# Pure_LFO.net
KiCad netlist of a schematic drawn in EAGLE
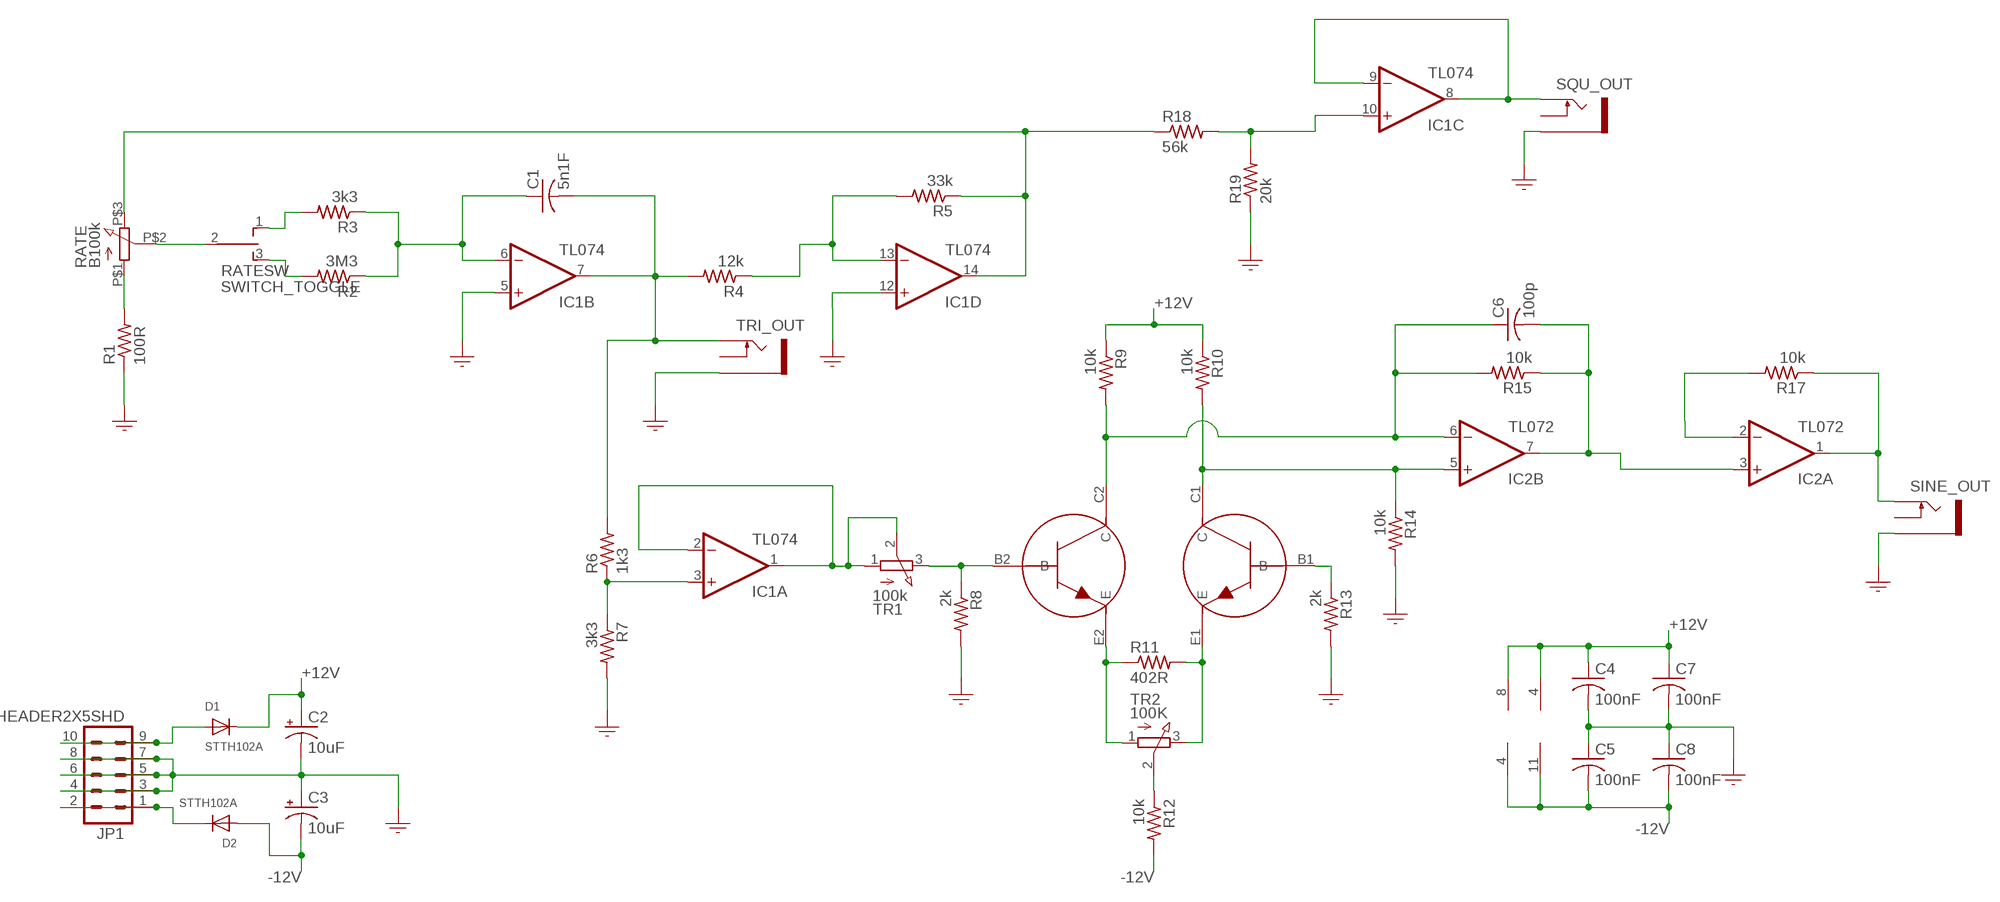
[diagram p0: schematic, sheet 1]

(export (version "E")
  (design (tool "Eeschema 10.0.6"))
  (components
    (comp (ref "C1")
      (value "5n1F")
      (footprint "eagle-import:C0805")
      (libsource (lib "eagle-import") (part "CAPACITOR-USC0805"))
    )
    (comp (ref "C2")
      (value "10uF")
      (footprint "eagle-import:153CLV-0505")
      (libsource (lib "eagle-import") (part "CAPACITOR_POL-US153CLV-0505"))
    )
    (comp (ref "C3")
      (value "10uF")
      (footprint "eagle-import:153CLV-0505")
      (libsource (lib "eagle-import") (part "CAPACITOR_POL-US153CLV-0505"))
    )
    (comp (ref "C4")
      (value "100nF")
      (footprint "eagle-import:C0805")
      (libsource (lib "eagle-import") (part "CAPACITOR-USC0805"))
    )
    (comp (ref "C5")
      (value "100nF")
      (footprint "eagle-import:C0805")
      (libsource (lib "eagle-import") (part "CAPACITOR-USC0805"))
    )
    (comp (ref "C6")
      (value "100p")
      (footprint "eagle-import:C0805")
      (libsource (lib "eagle-import") (part "CAPACITOR-USC0805"))
    )
    (comp (ref "C7")
      (value "100nF")
      (footprint "eagle-import:C0805")
      (libsource (lib "eagle-import") (part "CAPACITOR-USC0805"))
    )
    (comp (ref "C8")
      (value "100nF")
      (footprint "eagle-import:C0805")
      (libsource (lib "eagle-import") (part "CAPACITOR-USC0805"))
    )
    (comp (ref "D1")
      (value "STTH102A")
      (footprint "eagle-import:SMADIODE")
      (libsource (lib "eagle-import") (part "DIODESMA"))
    )
    (comp (ref "D2")
      (value "STTH102A")
      (footprint "eagle-import:SMADIODE")
      (libsource (lib "eagle-import") (part "DIODESMA"))
    )
    (comp (ref "IC1")
      (value "TL074")
      (footprint "eagle-import:SO14")
      (libsource (lib "eagle-import") (part "OPAMP_QUADD"))
    )
    (comp (ref "IC2")
      (value "TL072")
      (footprint "eagle-import:SO08")
      (libsource (lib "eagle-import") (part "OPAMP_DUALD"))
    )
    (comp (ref "JP1")
      (value "HEADER2X5SHD")
      (footprint "eagle-import:2X5-SHROUDED")
      (libsource (lib "eagle-import") (part "HEADER2X5SHD"))
    )
    (comp (ref "R1")
      (value "100R")
      (footprint "eagle-import:R0805")
      (libsource (lib "eagle-import") (part "RESISTOR_USR0805"))
    )
    (comp (ref "R2")
      (value "3M3")
      (footprint "eagle-import:R0805")
      (libsource (lib "eagle-import") (part "RESISTOR_USR0805"))
    )
    (comp (ref "R3")
      (value "3k3")
      (footprint "eagle-import:R0805")
      (libsource (lib "eagle-import") (part "RESISTOR_USR0805"))
    )
    (comp (ref "R4")
      (value "12k")
      (footprint "eagle-import:R0805")
      (libsource (lib "eagle-import") (part "RESISTOR_USR0805"))
    )
    (comp (ref "R5")
      (value "33k")
      (footprint "eagle-import:R0805")
      (libsource (lib "eagle-import") (part "RESISTOR_USR0805"))
    )
    (comp (ref "R6")
      (value "1k3")
      (footprint "eagle-import:R0805")
      (libsource (lib "eagle-import") (part "RESISTOR_USR0805"))
    )
    (comp (ref "R7")
      (value "3k3")
      (footprint "eagle-import:R0805")
      (libsource (lib "eagle-import") (part "RESISTOR_USR0805"))
    )
    (comp (ref "R8")
      (value "2k")
      (footprint "eagle-import:R0805")
      (libsource (lib "eagle-import") (part "RESISTOR_USR0805"))
    )
    (comp (ref "R9")
      (value "10k")
      (footprint "eagle-import:R0805")
      (libsource (lib "eagle-import") (part "RESISTOR_USR0805"))
    )
    (comp (ref "R10")
      (value "10k")
      (footprint "eagle-import:R0805")
      (libsource (lib "eagle-import") (part "RESISTOR_USR0805"))
    )
    (comp (ref "R11")
      (value "402R")
      (footprint "eagle-import:R0805")
      (libsource (lib "eagle-import") (part "RESISTOR_USR0805"))
    )
    (comp (ref "R12")
      (value "10k")
      (footprint "eagle-import:R0805")
      (libsource (lib "eagle-import") (part "RESISTOR_USR0805"))
    )
    (comp (ref "R13")
      (value "2k")
      (footprint "eagle-import:R0805")
      (libsource (lib "eagle-import") (part "RESISTOR_USR0805"))
    )
    (comp (ref "R14")
      (value "10k")
      (footprint "eagle-import:R0805")
      (libsource (lib "eagle-import") (part "RESISTOR_USR0805"))
    )
    (comp (ref "R15")
      (value "10k")
      (footprint "eagle-import:R0805")
      (libsource (lib "eagle-import") (part "RESISTOR_USR0805"))
    )
    (comp (ref "R17")
      (value "10k")
      (footprint "eagle-import:R0805")
      (libsource (lib "eagle-import") (part "RESISTOR_USR0805"))
    )
    (comp (ref "R18")
      (value "56k")
      (footprint "eagle-import:R0805")
      (libsource (lib "eagle-import") (part "RESISTOR_USR0805"))
    )
    (comp (ref "R19")
      (value "20k")
      (footprint "eagle-import:R0805")
      (libsource (lib "eagle-import") (part "RESISTOR_USR0805"))
    )
    (comp (ref "RATE")
      (value "B100k")
      (footprint "eagle-import:POTENTIOMETER_9MM")
      (libsource (lib "eagle-import") (part "RESISTOR_VARIABLE9MM_POT"))
    )
    (comp (ref "RATESW")
      (value "SWITCH_TOGGLE")
      (footprint "eagle-import:TOGGLE_SW")
      (libsource (lib "eagle-import") (part "SWITCH_TOGGLE"))
    )
    (comp (ref "SINE_OUT")
      (value "SOCKET_MONO_3.5MMPJ301M-12")
      (footprint "eagle-import:PJ301M-12")
      (libsource (lib "eagle-import") (part "SOCKET_MONO_3.5MMPJ301M-12"))
    )
    (comp (ref "SQU_OUT")
      (value "SOCKET_MONO_3.5MMPJ301M-12")
      (footprint "eagle-import:PJ301M-12")
      (libsource (lib "eagle-import") (part "SOCKET_MONO_3.5MMPJ301M-12"))
    )
    (comp (ref "T3")
      (value "DMMT3904W-7-F")
      (footprint "eagle-import:TRANS_PAIR")
      (libsource (lib "eagle-import") (part "TRANSISTOR_PAIR_NPN"))
    )
    (comp (ref "TR1")
      (value "100k")
      (footprint "eagle-import:TRIMMER_TH")
      (libsource (lib "eagle-import") (part "RESISTOR_VARIABLETRIMMER_TH"))
    )
    (comp (ref "TR2")
      (value "100K")
      (footprint "eagle-import:TRIMMER_TH")
      (libsource (lib "eagle-import") (part "RESISTOR_VARIABLETRIMMER_TH"))
    )
    (comp (ref "TRI_OUT")
      (value "SOCKET_MONO_3.5MMPJ301M-12")
      (footprint "eagle-import:PJ301M-12")
      (libsource (lib "eagle-import") (part "SOCKET_MONO_3.5MMPJ301M-12"))
    )
  )
  (nets
    (net (code "1") (name "/+12V") (class "Default")
      (node (ref "C2") (pin "+") (pinfunction "+_+") (pintype "passive"))
      (node (ref "C4") (pin "1") (pinfunction "1_1") (pintype "passive"))
      (node (ref "C7") (pin "1") (pinfunction "1_1") (pintype "passive"))
      (node (ref "D1") (pin "C") (pinfunction "C_C") (pintype "passive"))
      (node (ref "IC1") (pin "4") (pinfunction "V+_4") (pintype "power_in"))
      (node (ref "IC2") (pin "8") (pinfunction "V+_8") (pintype "power_in"))
      (node (ref "R10") (pin "1") (pinfunction "1_1") (pintype "passive"))
      (node (ref "R9") (pin "1") (pinfunction "1_1") (pintype "passive"))
    )
    (net (code "2") (name "/-12V") (class "Default")
      (node (ref "C3") (pin "-") (pinfunction "-_-") (pintype "passive"))
      (node (ref "C5") (pin "2") (pinfunction "2_2") (pintype "passive"))
      (node (ref "C8") (pin "2") (pinfunction "2_2") (pintype "passive"))
      (node (ref "D2") (pin "A") (pinfunction "A_A") (pintype "passive"))
      (node (ref "IC1") (pin "11") (pinfunction "V-_11") (pintype "power_in"))
      (node (ref "IC2") (pin "4") (pinfunction "V-_4") (pintype "power_in"))
      (node (ref "R12") (pin "2") (pinfunction "2_2") (pintype "passive"))
    )
    (net (code "3") (name "GND") (class "Default")
      (node (ref "C2") (pin "-") (pinfunction "-_-") (pintype "passive"))
      (node (ref "C3") (pin "+") (pinfunction "+_+") (pintype "passive"))
      (node (ref "C4") (pin "2") (pinfunction "2_2") (pintype "passive"))
      (node (ref "C5") (pin "1") (pinfunction "1_1") (pintype "passive"))
      (node (ref "C7") (pin "2") (pinfunction "2_2") (pintype "passive"))
      (node (ref "C8") (pin "1") (pinfunction "1_1") (pintype "passive"))
      (node (ref "IC1") (pin "12") (pinfunction "+IN_12") (pintype "input"))
      (node (ref "IC1") (pin "5") (pinfunction "+IN_5") (pintype "input"))
      (node (ref "JP1") (pin "3") (pinfunction "3_3") (pintype "passive"))
      (node (ref "JP1") (pin "4") (pinfunction "4_4") (pintype "passive"))
      (node (ref "JP1") (pin "5") (pinfunction "5_5") (pintype "passive"))
      (node (ref "JP1") (pin "6") (pinfunction "6_6") (pintype "passive"))
      (node (ref "JP1") (pin "7") (pinfunction "7_7") (pintype "passive"))
      (node (ref "JP1") (pin "8") (pinfunction "8_8") (pintype "passive"))
      (node (ref "R1") (pin "1") (pinfunction "1_1") (pintype "passive"))
      (node (ref "R13") (pin "2") (pinfunction "2_2") (pintype "passive"))
      (node (ref "R14") (pin "2") (pinfunction "2_2") (pintype "passive"))
      (node (ref "R19") (pin "1") (pinfunction "1_1") (pintype "passive"))
      (node (ref "R7") (pin "2") (pinfunction "2_2") (pintype "passive"))
      (node (ref "R8") (pin "2") (pinfunction "2_2") (pintype "passive"))
      (node (ref "SINE_OUT") (pin "GND") (pinfunction "SLEEVE_GND") (pintype "passive"))
      (node (ref "SQU_OUT") (pin "GND") (pinfunction "SLEEVE_GND") (pintype "passive"))
      (node (ref "TRI_OUT") (pin "GND") (pinfunction "SLEEVE_GND") (pintype "passive"))
    )
    (net (code "4") (name "Net-(D1-PadA)") (class "Default")
      (node (ref "D1") (pin "A") (pinfunction "A_A") (pintype "passive"))
      (node (ref "JP1") (pin "10") (pinfunction "10_10") (pintype "passive"))
      (node (ref "JP1") (pin "9") (pinfunction "9_9") (pintype "passive"))
    )
    (net (code "5") (name "Net-(D2-PadC)") (class "Default")
      (node (ref "D2") (pin "C") (pinfunction "C_C") (pintype "passive"))
      (node (ref "JP1") (pin "1") (pinfunction "1_1") (pintype "passive"))
      (node (ref "JP1") (pin "2") (pinfunction "2_2") (pintype "passive"))
    )
    (net (code "6") (name "Net-(IC1A-+IN)") (class "Default")
      (node (ref "IC1") (pin "3") (pinfunction "+IN_3") (pintype "input"))
      (node (ref "R6") (pin "1") (pinfunction "1_1") (pintype "passive"))
      (node (ref "R7") (pin "1") (pinfunction "1_1") (pintype "passive"))
    )
    (net (code "7") (name "Net-(IC1A--IN)") (class "Default")
      (node (ref "IC1") (pin "1") (pinfunction "OUT_1") (pintype "output"))
      (node (ref "IC1") (pin "2") (pinfunction "-IN_2") (pintype "input"))
      (node (ref "TR1") (pin "1") (pinfunction "1_1") (pintype "passive"))
      (node (ref "TR1") (pin "2") (pinfunction "2_2") (pintype "passive"))
    )
    (net (code "8") (name "Net-(IC1B--IN)") (class "Default")
      (node (ref "C1") (pin "1") (pinfunction "1_1") (pintype "passive"))
      (node (ref "IC1") (pin "6") (pinfunction "-IN_6") (pintype "input"))
      (node (ref "R2") (pin "1") (pinfunction "1_1") (pintype "passive"))
      (node (ref "R3") (pin "1") (pinfunction "1_1") (pintype "passive"))
    )
    (net (code "9") (name "Net-(IC1B-OUT)") (class "Default")
      (node (ref "C1") (pin "2") (pinfunction "2_2") (pintype "passive"))
      (node (ref "IC1") (pin "7") (pinfunction "OUT_7") (pintype "output"))
      (node (ref "R4") (pin "2") (pinfunction "2_2") (pintype "passive"))
      (node (ref "R6") (pin "2") (pinfunction "2_2") (pintype "passive"))
      (node (ref "TRI_OUT") (pin "TIP") (pinfunction "TIP_TIP") (pintype "passive"))
    )
    (net (code "10") (name "Net-(IC1C-+IN)") (class "Default")
      (node (ref "IC1") (pin "10") (pinfunction "+IN_10") (pintype "input"))
      (node (ref "R18") (pin "2") (pinfunction "2_2") (pintype "passive"))
      (node (ref "R19") (pin "2") (pinfunction "2_2") (pintype "passive"))
    )
    (net (code "11") (name "Net-(IC1C--IN)") (class "Default")
      (node (ref "IC1") (pin "8") (pinfunction "OUT_8") (pintype "output"))
      (node (ref "IC1") (pin "9") (pinfunction "-IN_9") (pintype "input"))
      (node (ref "SQU_OUT") (pin "TIP") (pinfunction "TIP_TIP") (pintype "passive"))
    )
    (net (code "12") (name "Net-(IC1D--IN)") (class "Default")
      (node (ref "IC1") (pin "13") (pinfunction "-IN_13") (pintype "input"))
      (node (ref "R4") (pin "1") (pinfunction "1_1") (pintype "passive"))
      (node (ref "R5") (pin "2") (pinfunction "2_2") (pintype "passive"))
    )
    (net (code "13") (name "Net-(IC1D-OUT)") (class "Default")
      (node (ref "IC1") (pin "14") (pinfunction "OUT_14") (pintype "output"))
      (node (ref "R18") (pin "1") (pinfunction "1_1") (pintype "passive"))
      (node (ref "R5") (pin "1") (pinfunction "1_1") (pintype "passive"))
      (node (ref "RATE") (pin "P$3") (pinfunction "3_P$3") (pintype "passive"))
    )
    (net (code "14") (name "Net-(IC2A-+IN)") (class "Default")
      (node (ref "C6") (pin "2") (pinfunction "2_2") (pintype "passive"))
      (node (ref "IC2") (pin "3") (pinfunction "+IN_3") (pintype "input"))
      (node (ref "IC2") (pin "7") (pinfunction "OUT_7") (pintype "output"))
      (node (ref "R15") (pin "1") (pinfunction "1_1") (pintype "passive"))
    )
    (net (code "15") (name "Net-(IC2A--IN)") (class "Default")
      (node (ref "IC2") (pin "2") (pinfunction "-IN_2") (pintype "input"))
      (node (ref "R17") (pin "2") (pinfunction "2_2") (pintype "passive"))
    )
    (net (code "16") (name "Net-(IC2A-OUT)") (class "Default")
      (node (ref "IC2") (pin "1") (pinfunction "OUT_1") (pintype "output"))
      (node (ref "R17") (pin "1") (pinfunction "1_1") (pintype "passive"))
      (node (ref "SINE_OUT") (pin "TIP") (pinfunction "TIP_TIP") (pintype "passive"))
    )
    (net (code "17") (name "Net-(IC2B-+IN)") (class "Default")
      (node (ref "IC2") (pin "5") (pinfunction "+IN_5") (pintype "input"))
      (node (ref "R10") (pin "2") (pinfunction "2_2") (pintype "passive"))
      (node (ref "R14") (pin "1") (pinfunction "1_1") (pintype "passive"))
      (node (ref "T3") (pin "C1") (pinfunction "C_C1") (pintype "bidirectional"))
    )
    (net (code "18") (name "Net-(IC2B--IN)") (class "Default")
      (node (ref "C6") (pin "1") (pinfunction "1_1") (pintype "passive"))
      (node (ref "IC2") (pin "6") (pinfunction "-IN_6") (pintype "input"))
      (node (ref "R15") (pin "2") (pinfunction "2_2") (pintype "passive"))
      (node (ref "R9") (pin "2") (pinfunction "2_2") (pintype "passive"))
      (node (ref "T3") (pin "C2") (pinfunction "C_C2") (pintype "bidirectional"))
    )
    (net (code "19") (name "Net-(R12-Pad1)") (class "Default")
      (node (ref "R12") (pin "1") (pinfunction "1_1") (pintype "passive"))
      (node (ref "TR2") (pin "2") (pinfunction "2_2") (pintype "passive"))
    )
    (net (code "20") (name "Net-(RATE-1)") (class "Default")
      (node (ref "R1") (pin "2") (pinfunction "2_2") (pintype "passive"))
      (node (ref "RATE") (pin "P$1") (pinfunction "1_P$1") (pintype "passive"))
    )
    (net (code "21") (name "Net-(RATE-2)") (class "Default")
      (node (ref "RATE") (pin "P$2") (pinfunction "2_P$2") (pintype "passive"))
      (node (ref "RATESW") (pin "2") (pinfunction "P_2") (pintype "passive"))
    )
    (net (code "22") (name "Net-(RATESW-O)") (class "Default")
      (node (ref "R3") (pin "2") (pinfunction "2_2") (pintype "passive"))
      (node (ref "RATESW") (pin "1") (pinfunction "O_1") (pintype "passive"))
    )
    (net (code "23") (name "Net-(RATESW-S)") (class "Default")
      (node (ref "R2") (pin "2") (pinfunction "2_2") (pintype "passive"))
      (node (ref "RATESW") (pin "3") (pinfunction "S_3") (pintype "passive"))
    )
    (net (code "24") (name "Net-(T3A-B)") (class "Default")
      (node (ref "R13") (pin "1") (pinfunction "1_1") (pintype "passive"))
      (node (ref "T3") (pin "B1") (pinfunction "B_B1") (pintype "bidirectional"))
    )
    (net (code "25") (name "Net-(T3A-E)") (class "Default")
      (node (ref "R11") (pin "2") (pinfunction "2_2") (pintype "passive"))
      (node (ref "T3") (pin "E1") (pinfunction "E_E1") (pintype "bidirectional"))
      (node (ref "TR2") (pin "3") (pinfunction "3_3") (pintype "passive"))
    )
    (net (code "26") (name "Net-(T3B-B)") (class "Default")
      (node (ref "R8") (pin "1") (pinfunction "1_1") (pintype "passive"))
      (node (ref "T3") (pin "B2") (pinfunction "B_B2") (pintype "bidirectional"))
      (node (ref "TR1") (pin "3") (pinfunction "3_3") (pintype "passive"))
    )
    (net (code "27") (name "Net-(T3B-E)") (class "Default")
      (node (ref "R11") (pin "1") (pinfunction "1_1") (pintype "passive"))
      (node (ref "T3") (pin "E2") (pinfunction "E_E2") (pintype "bidirectional"))
      (node (ref "TR2") (pin "1") (pinfunction "1_1") (pintype "passive"))
    )
    (net (code "28") (name "unconnected-(SINE_OUT-SWITCH-PadNORM)") (class "Default")
      (node (ref "SINE_OUT") (pin "NORM") (pinfunction "SWITCH_NORM") (pintype "passive"))
    )
    (net (code "29") (name "unconnected-(SQU_OUT-SWITCH-PadNORM)") (class "Default")
      (node (ref "SQU_OUT") (pin "NORM") (pinfunction "SWITCH_NORM") (pintype "passive"))
    )
    (net (code "30") (name "unconnected-(TRI_OUT-SWITCH-PadNORM)") (class "Default")
      (node (ref "TRI_OUT") (pin "NORM") (pinfunction "SWITCH_NORM") (pintype "passive"))
    )
  )
)
